# USB_UART.net
KiCad netlist of a schematic drawn in Altium Designer
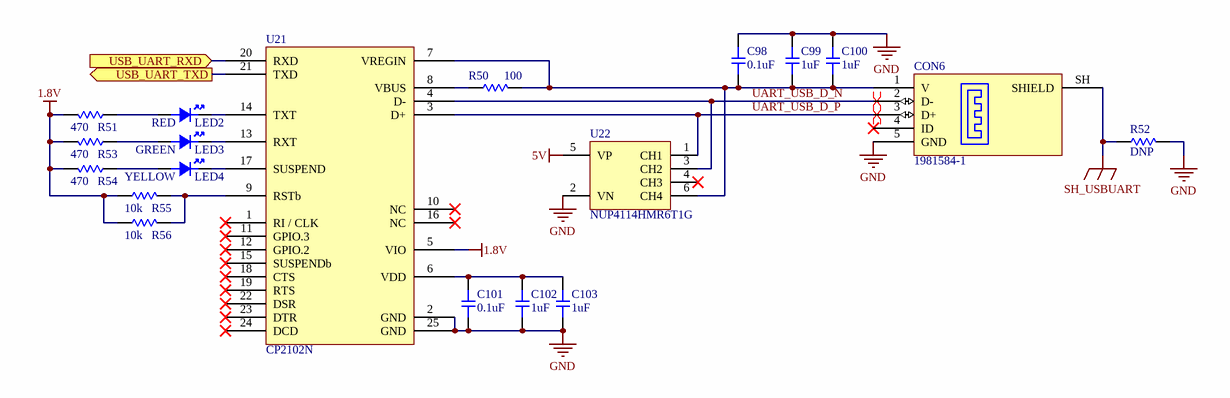
[diagram p0: USB_UART.SchDoc]

(export (version "E")
  (design (tool "Eeschema 10.0.6"))
  (components
    (comp (ref "C98")
      (value "0.1uF")
      (footprint "AMDC:0603-CAP")
      (description "Capacitor")
      (libsource (lib "AMDC") (part "Capacitor"))
    )
    (comp (ref "C99")
      (value "1uF")
      (footprint "AMDC:0603-CAP")
      (description "Capacitor")
      (libsource (lib "AMDC") (part "Capacitor"))
    )
    (comp (ref "C100")
      (value "1uF")
      (footprint "AMDC:0603-CAP")
      (description "Capacitor")
      (libsource (lib "AMDC") (part "Capacitor"))
    )
    (comp (ref "C101")
      (value "0.1uF")
      (footprint "AMDC:0603-CAP")
      (description "Capacitor")
      (libsource (lib "AMDC") (part "Capacitor"))
    )
    (comp (ref "C102")
      (value "1uF")
      (footprint "AMDC:0603-CAP")
      (description "Capacitor")
      (libsource (lib "AMDC") (part "Capacitor"))
    )
    (comp (ref "C103")
      (value "1uF")
      (footprint "AMDC:0603-CAP")
      (description "Capacitor")
      (libsource (lib "AMDC") (part "Capacitor"))
    )
    (comp (ref "CON6")
      (value "1981584-1")
      (footprint "AMDC:1981584-1")
      (description "CONN RCPT MICRO USB TYPE AB")
      (libsource (lib "AMDC") (part "1981584-1"))
    )
    (comp (ref "LED2")
      (value "RED")
      (footprint "AMDC:0603-LED")
      (fields (field (name "Comment") "LED"))
      (libsource (lib "AMDC") (part "LED"))
    )
    (comp (ref "LED3")
      (value "GREEN")
      (footprint "AMDC:0603-LED")
      (fields (field (name "Comment") "LED"))
      (libsource (lib "AMDC") (part "LED"))
    )
    (comp (ref "LED4")
      (value "YELLOW")
      (footprint "AMDC:0603-LED")
      (fields (field (name "Comment") "LED"))
      (libsource (lib "AMDC") (part "LED"))
    )
    (comp (ref "R50")
      (value "100")
      (footprint "AMDC:0603-RES")
      (description "Resistor")
      (libsource (lib "AMDC") (part "Resistor"))
    )
    (comp (ref "R51")
      (value "470")
      (footprint "AMDC:0603-RES")
      (description "Resistor")
      (libsource (lib "AMDC") (part "Resistor"))
    )
    (comp (ref "R52")
      (value "DNP")
      (footprint "AMDC:0603-RES")
      (description "Resistor")
      (libsource (lib "AMDC") (part "Resistor"))
    )
    (comp (ref "R53")
      (value "470")
      (footprint "AMDC:0603-RES")
      (description "Resistor")
      (libsource (lib "AMDC") (part "Resistor"))
    )
    (comp (ref "R54")
      (value "470")
      (footprint "AMDC:0603-RES")
      (description "Resistor")
      (libsource (lib "AMDC") (part "Resistor"))
    )
    (comp (ref "R55")
      (value "10k")
      (footprint "AMDC:0603-RES")
      (description "Resistor")
      (libsource (lib "AMDC") (part "Resistor"))
    )
    (comp (ref "R56")
      (value "10k")
      (footprint "AMDC:0603-RES")
      (description "Resistor")
      (libsource (lib "AMDC") (part "Resistor"))
    )
    (comp (ref "U21")
      (value "CP2102N")
      (footprint "AMDC:QFN50P400X400X80_HS-25N")
      (description "IC USB TO UART BRIDGE QFN24")
      (libsource (lib "AMDC") (part "CP2102N"))
    )
    (comp (ref "U22")
      (value "NUP4114HMR6T1G")
      (footprint "AMDC:TSOP95P280X110-6N")
      (description "TVS DIODE 5.5V 10V 6TSOP")
      (libsource (lib "AMDC") (part "NUP4114HMR6T1G"))
    )
  )
  (nets
    (net (code "1") (name "/UART_USB_D_N") (class "Default")
      (node (ref "CON6") (pin "2") (pinfunction "D-_2") (pintype "bidirectional"))
      (node (ref "U21") (pin "4") (pinfunction "D-_4") (pintype "passive"))
      (node (ref "U22") (pin "3") (pinfunction "CH2_3") (pintype "passive"))
    )
    (net (code "2") (name "/UART_USB_D_P") (class "Default")
      (node (ref "CON6") (pin "3") (pinfunction "D+_3") (pintype "bidirectional"))
      (node (ref "U21") (pin "3") (pinfunction "D+_3") (pintype "passive"))
      (node (ref "U22") (pin "1") (pinfunction "CH1_1") (pintype "passive"))
    )
    (net (code "3") (name "/USB_UART_RXD") (class "Default")
      (node (ref "U21") (pin "20") (pinfunction "RXD_20") (pintype "passive"))
    )
    (net (code "4") (name "/USB_UART_TXD") (class "Default")
      (node (ref "U21") (pin "21") (pinfunction "TXD_21") (pintype "passive"))
    )
    (net (code "5") (name "1.8V") (class "Default")
      (node (ref "R51") (pin "2") (pinfunction "2_2") (pintype "passive"))
      (node (ref "R53") (pin "2") (pinfunction "2_2") (pintype "passive"))
      (node (ref "R54") (pin "2") (pinfunction "2_2") (pintype "passive"))
      (node (ref "R55") (pin "1") (pinfunction "1_1") (pintype "passive"))
      (node (ref "R56") (pin "1") (pinfunction "1_1") (pintype "passive"))
      (node (ref "U21") (pin "5") (pinfunction "VIO_5") (pintype "passive"))
    )
    (net (code "6") (name "5V") (class "Default")
      (node (ref "U22") (pin "5") (pinfunction "VP_5") (pintype "passive"))
    )
    (net (code "7") (name "GND") (class "Default")
      (node (ref "C100") (pin "2") (pinfunction "2_2") (pintype "passive"))
      (node (ref "C101") (pin "1") (pinfunction "1_1") (pintype "passive"))
      (node (ref "C102") (pin "1") (pinfunction "1_1") (pintype "passive"))
      (node (ref "C103") (pin "1") (pinfunction "1_1") (pintype "passive"))
      (node (ref "C98") (pin "2") (pinfunction "2_2") (pintype "passive"))
      (node (ref "C99") (pin "2") (pinfunction "2_2") (pintype "passive"))
      (node (ref "CON6") (pin "5") (pinfunction "GND_5") (pintype "passive"))
      (node (ref "R52") (pin "2") (pinfunction "2_2") (pintype "passive"))
      (node (ref "U21") (pin "2") (pinfunction "GND_2") (pintype "passive"))
      (node (ref "U21") (pin "25") (pinfunction "GND_25") (pintype "passive"))
      (node (ref "U22") (pin "2") (pinfunction "VN_2") (pintype "passive"))
    )
    (net (code "8") (name "Net-(CON6-V)") (class "Default")
      (node (ref "C100") (pin "1") (pinfunction "1_1") (pintype "passive"))
      (node (ref "C98") (pin "1") (pinfunction "1_1") (pintype "passive"))
      (node (ref "C99") (pin "1") (pinfunction "1_1") (pintype "passive"))
      (node (ref "CON6") (pin "1") (pinfunction "V_1") (pintype "passive"))
      (node (ref "R50") (pin "2") (pinfunction "2_2") (pintype "passive"))
      (node (ref "U21") (pin "7") (pinfunction "VREGIN_7") (pintype "passive"))
      (node (ref "U22") (pin "6") (pinfunction "CH4_6") (pintype "passive"))
    )
    (net (code "9") (name "Net-(LED2-PadA)") (class "Default")
      (node (ref "LED2") (pin "A") (pinfunction "A_A") (pintype "passive"))
      (node (ref "R51") (pin "1") (pinfunction "1_1") (pintype "passive"))
    )
    (net (code "10") (name "Net-(LED3-PadA)") (class "Default")
      (node (ref "LED3") (pin "A") (pinfunction "A_A") (pintype "passive"))
      (node (ref "R53") (pin "1") (pinfunction "1_1") (pintype "passive"))
    )
    (net (code "11") (name "Net-(LED4-PadA)") (class "Default")
      (node (ref "LED4") (pin "A") (pinfunction "A_A") (pintype "passive"))
      (node (ref "R54") (pin "1") (pinfunction "1_1") (pintype "passive"))
    )
    (net (code "12") (name "Net-(U21-RSTb)") (class "Default")
      (node (ref "R55") (pin "2") (pinfunction "2_2") (pintype "passive"))
      (node (ref "R56") (pin "2") (pinfunction "2_2") (pintype "passive"))
      (node (ref "U21") (pin "9") (pinfunction "RSTb_9") (pintype "passive"))
    )
    (net (code "13") (name "Net-(U21-RXT)") (class "Default")
      (node (ref "LED3") (pin "C") (pinfunction "C_C") (pintype "passive"))
      (node (ref "U21") (pin "13") (pinfunction "RXT_13") (pintype "passive"))
    )
    (net (code "14") (name "Net-(U21-SUSPEND)") (class "Default")
      (node (ref "LED4") (pin "C") (pinfunction "C_C") (pintype "passive"))
      (node (ref "U21") (pin "17") (pinfunction "SUSPEND_17") (pintype "passive"))
    )
    (net (code "15") (name "Net-(U21-TXT)") (class "Default")
      (node (ref "LED2") (pin "C") (pinfunction "C_C") (pintype "passive"))
      (node (ref "U21") (pin "14") (pinfunction "TXT_14") (pintype "passive"))
    )
    (net (code "16") (name "Net-(U21-VBUS)") (class "Default")
      (node (ref "R50") (pin "1") (pinfunction "1_1") (pintype "passive"))
      (node (ref "U21") (pin "8") (pinfunction "VBUS_8") (pintype "passive"))
    )
    (net (code "17") (name "Net-(U21-VDD)") (class "Default")
      (node (ref "C101") (pin "2") (pinfunction "2_2") (pintype "passive"))
      (node (ref "C102") (pin "2") (pinfunction "2_2") (pintype "passive"))
      (node (ref "C103") (pin "2") (pinfunction "2_2") (pintype "passive"))
      (node (ref "U21") (pin "6") (pinfunction "VDD_6") (pintype "passive"))
    )
    (net (code "18") (name "SH_USBUART") (class "Default")
      (node (ref "CON6") (pin "SH") (pinfunction "SHIELD_SH") (pintype "passive"))
      (node (ref "R52") (pin "1") (pinfunction "1_1") (pintype "passive"))
    )
    (net (code "19") (name "unconnected-(CON6-ID-Pad4)") (class "Default")
      (node (ref "CON6") (pin "4") (pinfunction "ID_4") (pintype "passive+no_connect"))
    )
    (net (code "20") (name "unconnected-(U21-CTS-Pad18)") (class "Default")
      (node (ref "U21") (pin "18") (pinfunction "CTS_18") (pintype "passive+no_connect"))
    )
    (net (code "21") (name "unconnected-(U21-DCD-Pad24)") (class "Default")
      (node (ref "U21") (pin "24") (pinfunction "DCD_24") (pintype "passive+no_connect"))
    )
    (net (code "22") (name "unconnected-(U21-DSR-Pad22)") (class "Default")
      (node (ref "U21") (pin "22") (pinfunction "DSR_22") (pintype "passive+no_connect"))
    )
    (net (code "23") (name "unconnected-(U21-DTR-Pad23)") (class "Default")
      (node (ref "U21") (pin "23") (pinfunction "DTR_23") (pintype "passive+no_connect"))
    )
    (net (code "24") (name "unconnected-(U21-GPIO.2-Pad12)") (class "Default")
      (node (ref "U21") (pin "12") (pinfunction "GPIO.2_12") (pintype "passive+no_connect"))
    )
    (net (code "25") (name "unconnected-(U21-GPIO.3-Pad11)") (class "Default")
      (node (ref "U21") (pin "11") (pinfunction "GPIO.3_11") (pintype "passive+no_connect"))
    )
    (net (code "26") (name "unconnected-(U21-NC-Pad10)") (class "Default")
      (node (ref "U21") (pin "10") (pinfunction "NC_10") (pintype "passive+no_connect"))
    )
    (net (code "27") (name "unconnected-(U21-NC-Pad16)") (class "Default")
      (node (ref "U21") (pin "16") (pinfunction "NC_16") (pintype "passive+no_connect"))
    )
    (net (code "28") (name "unconnected-(U21-RI_{slash}_CLK-Pad1)") (class "Default")
      (node (ref "U21") (pin "1") (pinfunction "RI_/_CLK_1") (pintype "passive+no_connect"))
    )
    (net (code "29") (name "unconnected-(U21-RTS-Pad19)") (class "Default")
      (node (ref "U21") (pin "19") (pinfunction "RTS_19") (pintype "passive+no_connect"))
    )
    (net (code "30") (name "unconnected-(U21-SUSPENDb-Pad15)") (class "Default")
      (node (ref "U21") (pin "15") (pinfunction "SUSPENDb_15") (pintype "passive+no_connect"))
    )
    (net (code "31") (name "unconnected-(U22-CH3-Pad4)") (class "Default")
      (node (ref "U22") (pin "4") (pinfunction "CH3_4") (pintype "passive+no_connect"))
    )
  )
)
